# MPU_12x12.net
KiCad netlist of a schematic drawn in Altium Designer
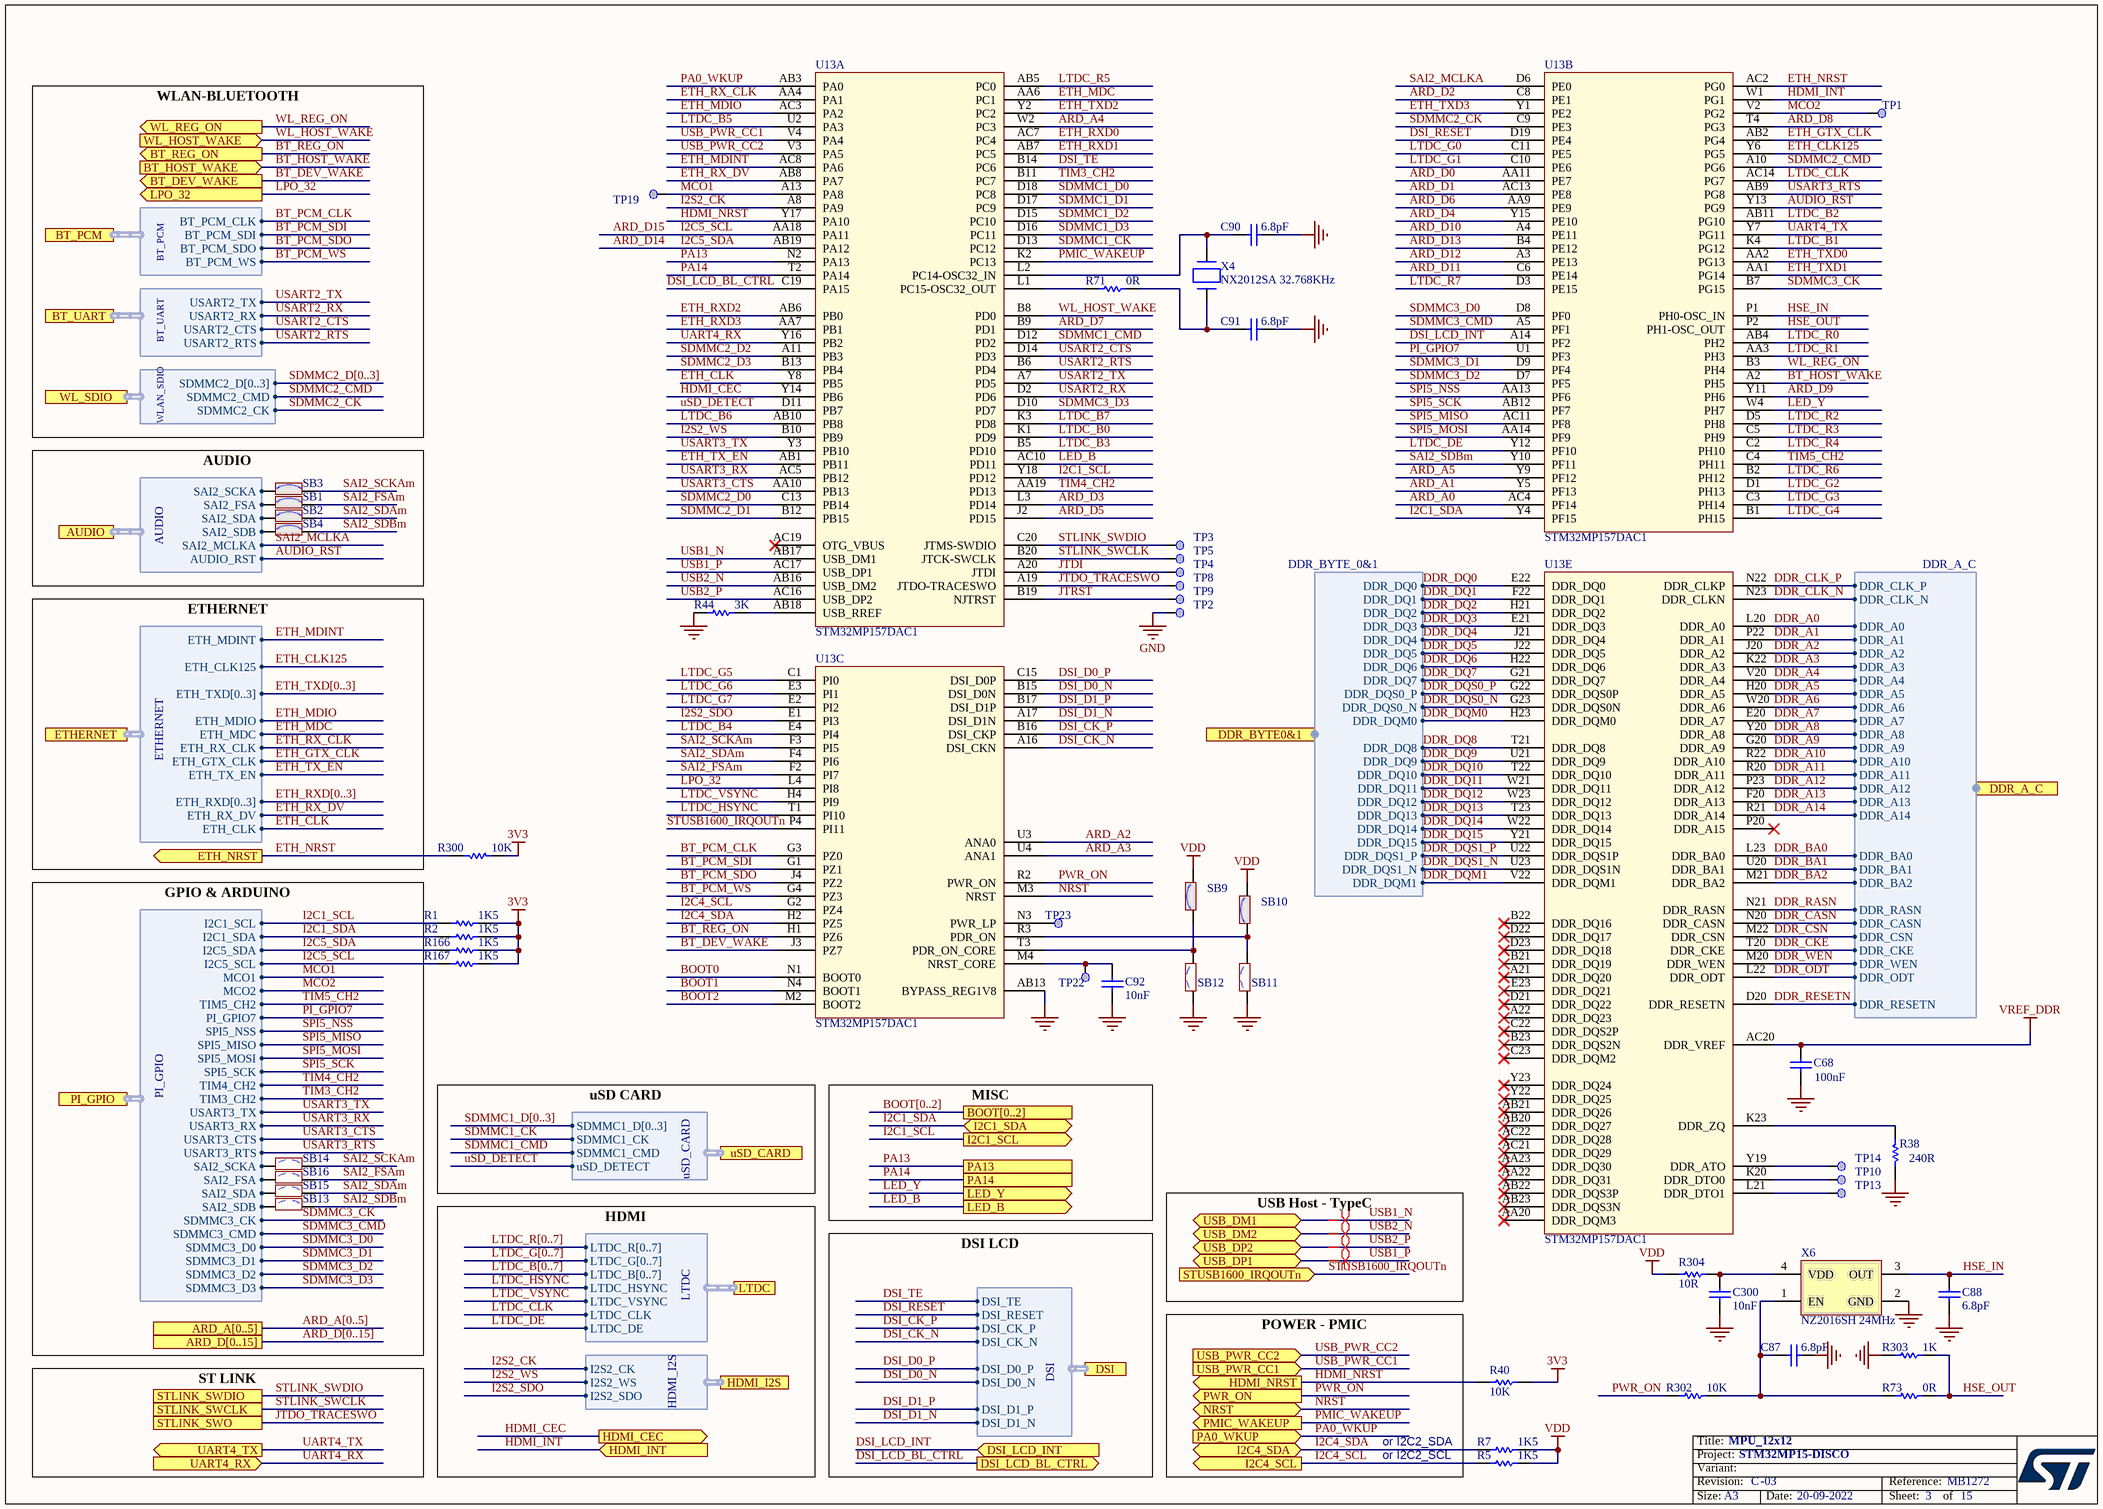
[diagram p0: MPU_12x12.SchDoc]

(export (version "E")
  (design (tool "Eeschema 10.0.6"))
  (components
    (comp (ref "C68")
      (value "100nF")
      (footprint "C0402")
      (description "Capacitor,100nF,16V,X7R,10%,0402")
      (fields
        (field (name "INTERNAL_PART_NUMBER") "MCD-00006")
        (field (name "MANUFACTURER_PART_NUMBER") "CC0402KRX7R7BB104")
        (field (name "PROVIDED_BY") "SUBCO")
      )
      (libsource (lib "MCD_PARTS_database") (part "Capacitor"))
    )
    (comp (ref "C87")
      (value "6.8pF")
      (footprint "C0402")
      (description "Capacitor, MLCC, 6.8pF, 50V, NPO, +-0.25pF, 0402, T=0.5mm")
      (fields
        (field (name "INTERNAL_PART_NUMBER") "MCD-00674")
        (field (name "MANUFACTURER_PART_NUMBER") "CC0402CRNPO9BN6R8")
        (field (name "PROVIDED_BY") "SUBCO")
      )
      (libsource (lib "MCD_PARTS_database") (part "Capacitor"))
    )
    (comp (ref "C88")
      (value "6.8pF")
      (footprint "C0402")
      (description "Capacitor, MLCC, 6.8pF, 50V, NPO, +-0.25pF, 0402, T=0.5mm")
      (fields
        (field (name "INTERNAL_PART_NUMBER") "MCD-00674")
        (field (name "MANUFACTURER_PART_NUMBER") "CC0402CRNPO9BN6R8")
        (field (name "PROVIDED_BY") "SUBCO")
      )
      (libsource (lib "MCD_PARTS_database") (part "Capacitor"))
    )
    (comp (ref "C90")
      (value "6.8pF")
      (footprint "C0402")
      (description "Capacitor, MLCC, 6.8pF, 50V, NPO, +-0.25pF, 0402, T=0.5mm")
      (fields
        (field (name "INTERNAL_PART_NUMBER") "MCD-00674")
        (field (name "MANUFACTURER_PART_NUMBER") "CC0402CRNPO9BN6R8")
        (field (name "PROVIDED_BY") "SUBCO")
      )
      (libsource (lib "MCD_PARTS_database") (part "Capacitor"))
    )
    (comp (ref "C91")
      (value "6.8pF")
      (footprint "C0402")
      (description "Capacitor, MLCC, 6.8pF, 50V, NPO, +-0.25pF, 0402, T=0.5mm")
      (fields
        (field (name "INTERNAL_PART_NUMBER") "MCD-00674")
        (field (name "MANUFACTURER_PART_NUMBER") "CC0402CRNPO9BN6R8")
        (field (name "PROVIDED_BY") "SUBCO")
      )
      (libsource (lib "MCD_PARTS_database") (part "Capacitor"))
    )
    (comp (ref "C92")
      (value "10nF")
      (footprint "C0402")
      (description "Capacitor, MLCC, 10nF, 16V, X7R, 10%, 0402, T=0.5mm")
      (fields
        (field (name "INTERNAL_PART_NUMBER") "MCD-00011")
        (field (name "MANUFACTURER_PART_NUMBER") "CC0402KRX7R7BB103")
        (field (name "PROVIDED_BY") "SUBCO")
      )
      (libsource (lib "MCD_PARTS_database") (part "Capacitor"))
    )
    (comp (ref "C300")
      (value "10nF")
      (footprint "C0402")
      (description "Capacitor, MLCC, 10nF, 16V, X7R, 10%, 0402, T=0.5mm")
      (fields
        (field (name "INTERNAL_PART_NUMBER") "MCD-00011")
        (field (name "MANUFACTURER_PART_NUMBER") "CC0402KRX7R7BB103")
        (field (name "PROVIDED_BY") "SUBCO")
      )
      (libsource (lib "MCD_PARTS_database") (part "Capacitor"))
    )
    (comp (ref "R1")
      (value "1K5")
      (footprint "R0402")
      (description "Resistor,1K5,0402,1%,1/16W")
      (fields
        (field (name "INTERNAL_PART_NUMBER") "MCD-00068")
        (field (name "MANUFACTURER_PART_NUMBER") "RC0402FR-071K5L")
        (field (name "PROVIDED_BY") "SUBCO")
      )
      (libsource (lib "MCD_PARTS_database") (part "Resistor"))
    )
    (comp (ref "R2")
      (value "1K5")
      (footprint "R0402")
      (description "Resistor,1K5,0402,1%,1/16W")
      (fields
        (field (name "INTERNAL_PART_NUMBER") "MCD-00068")
        (field (name "MANUFACTURER_PART_NUMBER") "RC0402FR-071K5L")
        (field (name "PROVIDED_BY") "SUBCO")
      )
      (libsource (lib "MCD_PARTS_database") (part "Resistor"))
    )
    (comp (ref "R5")
      (value "1K5")
      (footprint "R0402")
      (description "Resistor,1K5,0402,1%,1/16W")
      (fields
        (field (name "INTERNAL_PART_NUMBER") "MCD-00068")
        (field (name "MANUFACTURER_PART_NUMBER") "RC0402FR-071K5L")
        (field (name "PROVIDED_BY") "SUBCO")
      )
      (libsource (lib "MCD_PARTS_database") (part "Resistor"))
    )
    (comp (ref "R7")
      (value "1K5")
      (footprint "R0402")
      (description "Resistor,1K5,0402,1%,1/16W")
      (fields
        (field (name "INTERNAL_PART_NUMBER") "MCD-00068")
        (field (name "MANUFACTURER_PART_NUMBER") "RC0402FR-071K5L")
        (field (name "PROVIDED_BY") "SUBCO")
      )
      (libsource (lib "MCD_PARTS_database") (part "Resistor"))
    )
    (comp (ref "R38")
      (value "240R")
      (footprint "R0402")
      (description "Resistor,240R,0402,1%,1/16W")
      (fields
        (field (name "INTERNAL_PART_NUMBER") "MCD-00120")
        (field (name "MANUFACTURER_PART_NUMBER") "RC0402FR-07240RL")
        (field (name "PROVIDED_BY") "SUBCO")
      )
      (libsource (lib "MCD_PARTS_database") (part "Resistor"))
    )
    (comp (ref "R40")
      (value "10K")
      (footprint "R0402")
      (description "Resistor,10K,0402,1%,1/16W")
      (fields
        (field (name "INTERNAL_PART_NUMBER") "MCD-00053")
        (field (name "MANUFACTURER_PART_NUMBER") "RC0402FR-0710KL")
        (field (name "PROVIDED_BY") "SUBCO")
      )
      (libsource (lib "MCD_PARTS_database") (part "Resistor"))
    )
    (comp (ref "R44")
      (value "3K")
      (footprint "R0402")
      (description "Resistor,3K,0402,1%,1/16W")
      (fields
        (field (name "INTERNAL_PART_NUMBER") "MCD-00185")
        (field (name "MANUFACTURER_PART_NUMBER") "RC0402FR-073KL")
        (field (name "PROVIDED_BY") "SUBCO")
      )
      (libsource (lib "MCD_PARTS_database") (part "Resistor"))
    )
    (comp (ref "R71")
      (value "0R")
      (footprint "R0402")
      (description "Resistor,0R,0402,5%,1/16W")
      (fields
        (field (name "INTERNAL_PART_NUMBER") "MCD-00052")
        (field (name "MANUFACTURER_PART_NUMBER") "RC0402JR-070RL")
        (field (name "PROVIDED_BY") "SUBCO")
      )
      (libsource (lib "MCD_PARTS_database") (part "Resistor"))
    )
    (comp (ref "R73")
      (value "0R")
      (footprint "R0402")
      (description "Resistor,0R,0402,5%,1/16W")
      (fields
        (field (name "INTERNAL_PART_NUMBER") "MCD-00052")
        (field (name "MANUFACTURER_PART_NUMBER") "RC0402JR-070RL")
        (field (name "PROVIDED_BY") "SUBCO")
      )
      (libsource (lib "MCD_PARTS_database") (part "Resistor"))
    )
    (comp (ref "R166")
      (value "1K5")
      (footprint "R0402")
      (description "Resistor,1K5,0402,1%,1/16W")
      (fields
        (field (name "INTERNAL_PART_NUMBER") "MCD-00068")
        (field (name "MANUFACTURER_PART_NUMBER") "RC0402FR-071K5L")
        (field (name "PROVIDED_BY") "SUBCO")
      )
      (libsource (lib "MCD_PARTS_database") (part "Resistor"))
    )
    (comp (ref "R167")
      (value "1K5")
      (footprint "R0402")
      (description "Resistor,1K5,0402,1%,1/16W")
      (fields
        (field (name "INTERNAL_PART_NUMBER") "MCD-00068")
        (field (name "MANUFACTURER_PART_NUMBER") "RC0402FR-071K5L")
        (field (name "PROVIDED_BY") "SUBCO")
      )
      (libsource (lib "MCD_PARTS_database") (part "Resistor"))
    )
    (comp (ref "R300")
      (value "10K")
      (footprint "R0402")
      (description "Resistor,10K,0402,1%,1/16W")
      (fields
        (field (name "INTERNAL_PART_NUMBER") "MCD-00053")
        (field (name "MANUFACTURER_PART_NUMBER") "RC0402FR-0710KL")
        (field (name "PROVIDED_BY") "SUBCO")
      )
      (libsource (lib "MCD_PARTS_database") (part "Resistor"))
    )
    (comp (ref "R302")
      (value "10K")
      (footprint "R0402")
      (description "Resistor,10K,0402,1%,1/16W")
      (fields
        (field (name "INTERNAL_PART_NUMBER") "MCD-00053")
        (field (name "MANUFACTURER_PART_NUMBER") "RC0402FR-0710KL")
        (field (name "PROVIDED_BY") "SUBCO")
      )
      (libsource (lib "MCD_PARTS_database") (part "Resistor"))
    )
    (comp (ref "R303")
      (value "1K")
      (footprint "R0402")
      (description "Resistor,1K,0402,1%,1/16W")
      (fields
        (field (name "INTERNAL_PART_NUMBER") "MCD-00061")
        (field (name "MANUFACTURER_PART_NUMBER") "RC0402FR-071KL")
        (field (name "PROVIDED_BY") "SUBCO")
      )
      (libsource (lib "MCD_PARTS_database") (part "Resistor"))
    )
    (comp (ref "R304")
      (value "10R")
      (footprint "R0402")
      (description "Resistor,10R,0402,1%,1/16W")
      (fields
        (field (name "INTERNAL_PART_NUMBER") "MCD-00358")
        (field (name "MANUFACTURER_PART_NUMBER") "RC0402FR-0710RL")
        (field (name "PROVIDED_BY") "SUBCO")
      )
      (libsource (lib "MCD_PARTS_database") (part "Resistor"))
    )
    (comp (ref "SB1")
      (value "~")
      (footprint "SOLDER-BRIDGE_R0603-0R")
      (description "Solder Bridge ON")
      (fields
        (field (name "INTERNAL_PART_NUMBER") "MCD-00071")
        (field (name "MANUFACTURER") "YAGEO")
        (field (name "PROVIDED_BY") "SUBCO")
      )
      (libsource (lib "MCD_PARTS_database") (part "SB_ON"))
    )
    (comp (ref "SB2")
      (value "~")
      (footprint "SOLDER-BRIDGE_R0603-0R")
      (description "Solder Bridge ON")
      (fields
        (field (name "INTERNAL_PART_NUMBER") "MCD-00071")
        (field (name "MANUFACTURER") "YAGEO")
        (field (name "PROVIDED_BY") "SUBCO")
      )
      (libsource (lib "MCD_PARTS_database") (part "SB_ON"))
    )
    (comp (ref "SB3")
      (value "~")
      (footprint "SOLDER-BRIDGE_R0603-0R")
      (description "Solder Bridge ON")
      (fields
        (field (name "INTERNAL_PART_NUMBER") "MCD-00071")
        (field (name "MANUFACTURER") "YAGEO")
        (field (name "PROVIDED_BY") "SUBCO")
      )
      (libsource (lib "MCD_PARTS_database") (part "SB_ON"))
    )
    (comp (ref "SB4")
      (value "~")
      (footprint "SOLDER-BRIDGE_R0603-0R")
      (description "Solder Bridge ON")
      (fields
        (field (name "INTERNAL_PART_NUMBER") "MCD-00071")
        (field (name "MANUFACTURER") "YAGEO")
        (field (name "PROVIDED_BY") "SUBCO")
      )
      (libsource (lib "MCD_PARTS_database") (part "SB_ON"))
    )
    (comp (ref "SB9")
      (value "~")
      (footprint "SOLDER-BRIDGE_R0603-0R")
      (description "Solder Bridge ON")
      (fields
        (field (name "INTERNAL_PART_NUMBER") "MCD-00071")
        (field (name "MANUFACTURER") "YAGEO")
        (field (name "PROVIDED_BY") "SUBCO")
      )
      (libsource (lib "") (part "SB_ON_1"))
    )
    (comp (ref "SB10")
      (value "~")
      (footprint "SOLDER-BRIDGE_R0603-0R")
      (description "Solder Bridge ON")
      (fields
        (field (name "INTERNAL_PART_NUMBER") "MCD-00071")
        (field (name "MANUFACTURER") "YAGEO")
        (field (name "PROVIDED_BY") "SUBCO")
      )
      (libsource (lib "") (part "SB_ON_1"))
    )
    (comp (ref "SB11")
      (value "~")
      (footprint "SOLDER-BRIDGE_R0603-0R")
      (description "Solder Bridge OFF")
      (fields
        (field (name "INTERNAL_PART_NUMBER") "MCD-00072")
        (field (name "MANUFACTURER") "YAGEO")
        (field (name "PROVIDED_BY") "SUBCO")
      )
      (libsource (lib "") (part "SB_OFF_1"))
    )
    (comp (ref "SB12")
      (value "~")
      (footprint "SOLDER-BRIDGE_R0603-0R")
      (description "Solder Bridge OFF")
      (fields
        (field (name "INTERNAL_PART_NUMBER") "MCD-00072")
        (field (name "MANUFACTURER") "YAGEO")
        (field (name "PROVIDED_BY") "SUBCO")
      )
      (libsource (lib "") (part "SB_OFF_1"))
    )
    (comp (ref "SB13")
      (value "~")
      (footprint "SOLDER-BRIDGE_R0603-0R")
      (description "Solder Bridge OFF")
      (fields
        (field (name "INTERNAL_PART_NUMBER") "MCD-00072")
        (field (name "MANUFACTURER") "YAGEO")
        (field (name "PROVIDED_BY") "SUBCO")
      )
      (libsource (lib "MCD_PARTS_database") (part "SB_OFF"))
    )
    (comp (ref "SB14")
      (value "~")
      (footprint "SOLDER-BRIDGE_R0603-0R")
      (description "Solder Bridge OFF")
      (fields
        (field (name "INTERNAL_PART_NUMBER") "MCD-00072")
        (field (name "MANUFACTURER") "YAGEO")
        (field (name "PROVIDED_BY") "SUBCO")
      )
      (libsource (lib "MCD_PARTS_database") (part "SB_OFF"))
    )
    (comp (ref "SB15")
      (value "~")
      (footprint "SOLDER-BRIDGE_R0603-0R")
      (description "Solder Bridge OFF")
      (fields
        (field (name "INTERNAL_PART_NUMBER") "MCD-00072")
        (field (name "MANUFACTURER") "YAGEO")
        (field (name "PROVIDED_BY") "SUBCO")
      )
      (libsource (lib "MCD_PARTS_database") (part "SB_OFF"))
    )
    (comp (ref "SB16")
      (value "~")
      (footprint "SOLDER-BRIDGE_R0603-0R")
      (description "Solder Bridge OFF")
      (fields
        (field (name "INTERNAL_PART_NUMBER") "MCD-00072")
        (field (name "MANUFACTURER") "YAGEO")
        (field (name "PROVIDED_BY") "SUBCO")
      )
      (libsource (lib "MCD_PARTS_database") (part "SB_OFF"))
    )
    (comp (ref "TP1")
      (value "Test Point")
      (footprint "TP_SMD_1MM")
      (description "Test Point 1mm")
      (fields
        (field (name "INTERNAL_PART_NUMBER") "MCD-00074")
        (field (name "MANUFACTURER_PART_NUMBER") "n/a")
      )
      (libsource (lib "MCD_PARTS_database") (part "Test Point"))
    )
    (comp (ref "TP2")
      (value "Test Point")
      (footprint "TP_SMD_1MM")
      (description "Test Point 1mm")
      (fields
        (field (name "INTERNAL_PART_NUMBER") "MCD-00074")
        (field (name "MANUFACTURER_PART_NUMBER") "n/a")
      )
      (libsource (lib "MCD_PARTS_database") (part "Test Point"))
    )
    (comp (ref "TP3")
      (value "Test Point")
      (footprint "TP_SMD_1MM")
      (description "Test Point 1mm")
      (fields
        (field (name "INTERNAL_PART_NUMBER") "MCD-00074")
        (field (name "MANUFACTURER_PART_NUMBER") "n/a")
      )
      (libsource (lib "MCD_PARTS_database") (part "Test Point"))
    )
    (comp (ref "TP4")
      (value "Test Point")
      (footprint "TP_SMD_1MM")
      (description "Test Point 1mm")
      (fields
        (field (name "INTERNAL_PART_NUMBER") "MCD-00074")
        (field (name "MANUFACTURER_PART_NUMBER") "n/a")
      )
      (libsource (lib "MCD_PARTS_database") (part "Test Point"))
    )
    (comp (ref "TP5")
      (value "Test Point")
      (footprint "TP_SMD_1MM")
      (description "Test Point 1mm")
      (fields
        (field (name "INTERNAL_PART_NUMBER") "MCD-00074")
        (field (name "MANUFACTURER_PART_NUMBER") "n/a")
      )
      (libsource (lib "MCD_PARTS_database") (part "Test Point"))
    )
    (comp (ref "TP8")
      (value "Test Point")
      (footprint "TP_SMD_1MM")
      (description "Test Point 1mm")
      (fields
        (field (name "INTERNAL_PART_NUMBER") "MCD-00074")
        (field (name "MANUFACTURER_PART_NUMBER") "n/a")
      )
      (libsource (lib "MCD_PARTS_database") (part "Test Point"))
    )
    (comp (ref "TP9")
      (value "Test Point")
      (footprint "TP_SMD_1MM")
      (description "Test Point 1mm")
      (fields
        (field (name "INTERNAL_PART_NUMBER") "MCD-00074")
        (field (name "MANUFACTURER_PART_NUMBER") "n/a")
      )
      (libsource (lib "MCD_PARTS_database") (part "Test Point"))
    )
    (comp (ref "TP10")
      (value "~")
      (footprint "TP_SMD_0-6MM")
      (description "Test Point 0.6mm")
      (fields (field (name "INTERNAL_PART_NUMBER") "MCD-00631"))
      (libsource (lib "MCD_PARTS_database") (part "Test Point"))
    )
    (comp (ref "TP13")
      (value "~")
      (footprint "TP_SMD_0-6MM")
      (description "Test Point 0.6mm")
      (fields (field (name "INTERNAL_PART_NUMBER") "MCD-00631"))
      (libsource (lib "MCD_PARTS_database") (part "Test Point"))
    )
    (comp (ref "TP14")
      (value "~")
      (footprint "TP_SMD_0-6MM")
      (description "Test Point 0.6mm")
      (fields (field (name "INTERNAL_PART_NUMBER") "MCD-00631"))
      (libsource (lib "MCD_PARTS_database") (part "Test Point"))
    )
    (comp (ref "TP19")
      (value "Test Point")
      (footprint "TP_SMD_1MM")
      (description "Test Point 1mm")
      (fields
        (field (name "INTERNAL_PART_NUMBER") "MCD-00074")
        (field (name "MANUFACTURER_PART_NUMBER") "n/a")
      )
      (libsource (lib "") (part "Test Point_2"))
    )
    (comp (ref "TP22")
      (value "Test Point")
      (footprint "TP_SMD_1MM")
      (description "Test Point 1mm")
      (fields
        (field (name "INTERNAL_PART_NUMBER") "MCD-00074")
        (field (name "MANUFACTURER_PART_NUMBER") "n/a")
      )
      (libsource (lib "") (part "Test Point_1"))
    )
    (comp (ref "TP23")
      (value "Test Point")
      (footprint "TP_SMD_1MM")
      (description "Test Point 1mm")
      (fields
        (field (name "INTERNAL_PART_NUMBER") "MCD-00074")
        (field (name "MANUFACTURER_PART_NUMBER") "n/a")
      )
      (libsource (lib "MCD_PARTS_database") (part "Test Point"))
    )
    (comp (ref "U13")
      (value "STM32MP157DAC1")
      (footprint "ICC_TFBGA361_12X12_STM32MP157CAC3_P050-065")
      (description "MPU TFBGA12x12 without crypto increased frequency")
      (fields
        (field (name "INTERNAL_PART_NUMBER") "MCD-02020")
        (field (name "MANUFACTURER") "STMICROELECTRONICS")
        (field (name "PROVIDED_BY") "SUBCO with ST control")
      )
      (libsource (lib "MCD_PARTS_database") (part "STM32MP157DAC1"))
    )
    (comp (ref "X4")
      (value "NX2012SA 32.768KHz")
      (footprint "CRY_NX2012SA_2P")
      (description "Crystal 32.768kHz, 6pF, -+20PPM, R=80K, SMD")
      (fields
        (field (name "INTERNAL_PART_NUMBER") "MCD-01479")
        (field (name "MANUFACTURER_PART_NUMBER") "NX2012SA 32.768KHz EXS00A-MU00527")
        (field (name "PROVIDED_BY") "SUBCO")
      )
      (libsource (lib "MCD_PARTS_database") (part "XTAL_2_PINS"))
    )
    (comp (ref "X6")
      (value "NZ2016SH 24MHz")
      (footprint "CRY_NZ2016SH_4P")
      (description "Oscillator 24Mhz, +-50ppm, Vcc:3.3V typ (1.62V min), square wave: [0.1Vcc;0.9Vcc], Enable pin")
      (fields
        (field (name "INTERNAL_PART_NUMBER") "MCD-01627")
        (field (name "MANUFACTURER_PART_NUMBER") "NZ2016SH 24MHz END4869F")
        (field (name "PROVIDED_BY") "SUBCO")
      )
      (libsource (lib "MCD_PARTS_database") (part "OSCILLATOR_4_PINS"))
    )
  )
  (nets
    (net (code "13") (name "/ARD_A0") (class "Default")
      (node (ref "U13") (pin "AC4") (pinfunction "PF14_AC4") (pintype "passive"))
    )
    (net (code "14") (name "/ARD_A1") (class "Default")
      (node (ref "U13") (pin "Y5") (pinfunction "PF13_Y5") (pintype "passive"))
    )
    (net (code "15") (name "/ARD_A2") (class "Default")
      (node (ref "U13") (pin "U3") (pinfunction "ANA0_U3") (pintype "passive"))
    )
    (net (code "16") (name "/ARD_A3") (class "Default")
      (node (ref "U13") (pin "U4") (pinfunction "ANA1_U4") (pintype "passive"))
    )
    (net (code "17") (name "/ARD_A4") (class "Default")
      (node (ref "U13") (pin "W2") (pinfunction "PC3_W2") (pintype "passive"))
    )
    (net (code "18") (name "/ARD_A5") (class "Default")
      (node (ref "U13") (pin "Y9") (pinfunction "PF12_Y9") (pintype "passive"))
    )
    (net (code "20") (name "/ARD_D0") (class "Default")
      (node (ref "U13") (pin "AA11") (pinfunction "PE7_AA11") (pintype "passive"))
    )
    (net (code "21") (name "/ARD_D1") (class "Default")
      (node (ref "U13") (pin "AC13") (pinfunction "PE8_AC13") (pintype "passive"))
    )
    (net (code "22") (name "/ARD_D2") (class "Default")
      (node (ref "U13") (pin "C8") (pinfunction "PE1_C8") (pintype "passive"))
    )
    (net (code "23") (name "/ARD_D3") (class "Default")
      (node (ref "U13") (pin "L3") (pinfunction "PD14_L3") (pintype "passive"))
    )
    (net (code "24") (name "/ARD_D4") (class "Default")
      (node (ref "U13") (pin "Y15") (pinfunction "PE10_Y15") (pintype "passive"))
    )
    (net (code "25") (name "/ARD_D5") (class "Default")
      (node (ref "U13") (pin "J2") (pinfunction "PD15_J2") (pintype "passive"))
    )
    (net (code "26") (name "/ARD_D6") (class "Default")
      (node (ref "U13") (pin "AA9") (pinfunction "PE9_AA9") (pintype "passive"))
    )
    (net (code "27") (name "/ARD_D7") (class "Default")
      (node (ref "U13") (pin "B9") (pinfunction "PD1_B9") (pintype "passive"))
    )
    (net (code "28") (name "/ARD_D8") (class "Default")
      (node (ref "U13") (pin "T4") (pinfunction "PG3_T4") (pintype "passive"))
    )
    (net (code "29") (name "/ARD_D9") (class "Default")
      (node (ref "U13") (pin "Y11") (pinfunction "PH6_Y11") (pintype "passive"))
    )
    (net (code "30") (name "/ARD_D10") (class "Default")
      (node (ref "U13") (pin "A4") (pinfunction "PE11_A4") (pintype "passive"))
    )
    (net (code "31") (name "/ARD_D11") (class "Default")
      (node (ref "U13") (pin "C6") (pinfunction "PE14_C6") (pintype "passive"))
    )
    (net (code "32") (name "/ARD_D12") (class "Default")
      (node (ref "U13") (pin "A3") (pinfunction "PE13_A3") (pintype "passive"))
    )
    (net (code "33") (name "/ARD_D13") (class "Default")
      (node (ref "U13") (pin "B4") (pinfunction "PE12_B4") (pintype "passive"))
    )
    (net (code "34") (name "/ARD_D14") (class "Default")
      (node (ref "R166") (pin "2") (pinfunction "2_2") (pintype "passive"))
      (node (ref "U13") (pin "AB19") (pinfunction "PA12_AB19") (pintype "passive"))
    )
    (net (code "35") (name "/ARD_D15") (class "Default")
      (node (ref "R167") (pin "2") (pinfunction "2_2") (pintype "passive"))
      (node (ref "U13") (pin "AA18") (pinfunction "PA11_AA18") (pintype "passive"))
    )
    (net (code "37") (name "/AUDIO_RST") (class "Default")
      (node (ref "U13") (pin "Y13") (pinfunction "PG9_Y13") (pintype "passive"))
    )
    (net (code "38") (name "/BOOT0") (class "Default")
      (node (ref "U13") (pin "N1") (pinfunction "BOOT0_N1") (pintype "passive"))
    )
    (net (code "39") (name "/BOOT1") (class "Default")
      (node (ref "U13") (pin "N4") (pinfunction "BOOT1_N4") (pintype "passive"))
    )
    (net (code "40") (name "/BOOT2") (class "Default")
      (node (ref "U13") (pin "M2") (pinfunction "BOOT2_M2") (pintype "passive"))
    )
    (net (code "42") (name "/BT_DEV_WAKE") (class "Default")
      (node (ref "U13") (pin "J3") (pinfunction "PZ7_J3") (pintype "passive"))
    )
    (net (code "43") (name "/BT_HOST_WAKE") (class "Default")
      (node (ref "U13") (pin "A2") (pinfunction "PH5_A2") (pintype "passive"))
    )
    (net (code "44") (name "/BT_PCM_CLK") (class "Default")
      (node (ref "U13") (pin "G3") (pinfunction "PZ0_G3") (pintype "passive"))
    )
    (net (code "45") (name "/BT_PCM_SDI") (class "Default")
      (node (ref "U13") (pin "G1") (pinfunction "PZ1_G1") (pintype "passive"))
    )
    (net (code "46") (name "/BT_PCM_SDO") (class "Default")
      (node (ref "U13") (pin "J4") (pinfunction "PZ2_J4") (pintype "passive"))
    )
    (net (code "47") (name "/BT_PCM_WS") (class "Default")
      (node (ref "U13") (pin "G4") (pinfunction "PZ3_G4") (pintype "passive"))
    )
    (net (code "48") (name "/BT_REG_ON") (class "Default")
      (node (ref "U13") (pin "H1") (pinfunction "PZ6_H1") (pintype "passive"))
    )
    (net (code "49") (name "/DDR_A0") (class "Default")
      (node (ref "U13") (pin "L20") (pinfunction "DDR_A0_L20") (pintype "passive"))
    )
    (net (code "50") (name "/DDR_A1") (class "Default")
      (node (ref "U13") (pin "P22") (pinfunction "DDR_A1_P22") (pintype "passive"))
    )
    (net (code "51") (name "/DDR_A2") (class "Default")
      (node (ref "U13") (pin "J20") (pinfunction "DDR_A2_J20") (pintype "passive"))
    )
    (net (code "52") (name "/DDR_A3") (class "Default")
      (node (ref "U13") (pin "K22") (pinfunction "DDR_A3_K22") (pintype "passive"))
    )
    (net (code "53") (name "/DDR_A4") (class "Default")
      (node (ref "U13") (pin "V20") (pinfunction "DDR_A4_V20") (pintype "passive"))
    )
    (net (code "54") (name "/DDR_A5") (class "Default")
      (node (ref "U13") (pin "H20") (pinfunction "DDR_A5_H20") (pintype "passive"))
    )
    (net (code "55") (name "/DDR_A6") (class "Default")
      (node (ref "U13") (pin "W20") (pinfunction "DDR_A6_W20") (pintype "passive"))
    )
    (net (code "56") (name "/DDR_A7") (class "Default")
      (node (ref "U13") (pin "E20") (pinfunction "DDR_A7_E20") (pintype "passive"))
    )
    (net (code "57") (name "/DDR_A8") (class "Default")
      (node (ref "U13") (pin "Y20") (pinfunction "DDR_A8_Y20") (pintype "passive"))
    )
    (net (code "58") (name "/DDR_A9") (class "Default")
      (node (ref "U13") (pin "G20") (pinfunction "DDR_A9_G20") (pintype "passive"))
    )
    (net (code "59") (name "/DDR_A10") (class "Default")
      (node (ref "U13") (pin "R22") (pinfunction "DDR_A10_R22") (pintype "passive"))
    )
    (net (code "60") (name "/DDR_A11") (class "Default")
      (node (ref "U13") (pin "R20") (pinfunction "DDR_A11_R20") (pintype "passive"))
    )
    (net (code "61") (name "/DDR_A12") (class "Default")
      (node (ref "U13") (pin "P23") (pinfunction "DDR_A12_P23") (pintype "passive"))
    )
    (net (code "62") (name "/DDR_A13") (class "Default")
      (node (ref "U13") (pin "F20") (pinfunction "DDR_A13_F20") (pintype "passive"))
    )
    (net (code "63") (name "/DDR_A14") (class "Default")
      (node (ref "U13") (pin "R21") (pinfunction "DDR_A14_R21") (pintype "passive"))
    )
    (net (code "64") (name "/DDR_BA0") (class "Default")
      (node (ref "U13") (pin "L23") (pinfunction "DDR_BA0_L23") (pintype "passive"))
    )
    (net (code "65") (name "/DDR_BA1") (class "Default")
      (node (ref "U13") (pin "U20") (pinfunction "DDR_BA1_U20") (pintype "passive"))
    )
    (net (code "66") (name "/DDR_BA2") (class "Default")
      (node (ref "U13") (pin "M21") (pinfunction "DDR_BA2_M21") (pintype "passive"))
    )
    (net (code "67") (name "/DDR_CASN") (class "Default")
      (node (ref "U13") (pin "N20") (pinfunction "DDR_CASN_N20") (pintype "passive"))
    )
    (net (code "68") (name "/DDR_CKE") (class "Default")
      (node (ref "U13") (pin "T20") (pinfunction "DDR_CKE_T20") (pintype "passive"))
    )
    (net (code "69") (name "/DDR_CLK_N") (class "Default")
      (node (ref "U13") (pin "N23") (pinfunction "DDR_CLKN_N23") (pintype "passive"))
    )
    (net (code "70") (name "/DDR_CLK_P") (class "Default")
      (node (ref "U13") (pin "N22") (pinfunction "DDR_CLKP_N22") (pintype "passive"))
    )
    (net (code "71") (name "/DDR_CSN") (class "Default")
      (node (ref "U13") (pin "M22") (pinfunction "DDR_CSN_M22") (pintype "passive"))
    )
    (net (code "72") (name "/DDR_DQ0") (class "Default")
      (node (ref "U13") (pin "E22") (pinfunction "DDR_DQ0_E22") (pintype "passive"))
    )
    (net (code "73") (name "/DDR_DQ1") (class "Default")
      (node (ref "U13") (pin "F22") (pinfunction "DDR_DQ1_F22") (pintype "passive"))
    )
    (net (code "74") (name "/DDR_DQ2") (class "Default")
      (node (ref "U13") (pin "H21") (pinfunction "DDR_DQ2_H21") (pintype "passive"))
    )
    (net (code "75") (name "/DDR_DQ3") (class "Default")
      (node (ref "U13") (pin "E21") (pinfunction "DDR_DQ3_E21") (pintype "passive"))
    )
    (net (code "76") (name "/DDR_DQ4") (class "Default")
      (node (ref "U13") (pin "J21") (pinfunction "DDR_DQ4_J21") (pintype "passive"))
    )
    (net (code "77") (name "/DDR_DQ5") (class "Default")
      (node (ref "U13") (pin "J22") (pinfunction "DDR_DQ5_J22") (pintype "passive"))
    )
    (net (code "78") (name "/DDR_DQ6") (class "Default")
      (node (ref "U13") (pin "H22") (pinfunction "DDR_DQ6_H22") (pintype "passive"))
    )
    (net (code "79") (name "/DDR_DQ7") (class "Default")
      (node (ref "U13") (pin "G21") (pinfunction "DDR_DQ7_G21") (pintype "passive"))
    )
    (net (code "80") (name "/DDR_DQ8") (class "Default")
      (node (ref "U13") (pin "T21") (pinfunction "DDR_DQ8_T21") (pintype "passive"))
    )
    (net (code "81") (name "/DDR_DQ9") (class "Default")
      (node (ref "U13") (pin "U21") (pinfunction "DDR_DQ9_U21") (pintype "passive"))
    )
    (net (code "82") (name "/DDR_DQ10") (class "Default")
      (node (ref "U13") (pin "T22") (pinfunction "DDR_DQ10_T22") (pintype "passive"))
    )
    (net (code "83") (name "/DDR_DQ11") (class "Default")
      (node (ref "U13") (pin "W21") (pinfunction "DDR_DQ11_W21") (pintype "passive"))
    )
    (net (code "84") (name "/DDR_DQ12") (class "Default")
      (node (ref "U13") (pin "W23") (pinfunction "DDR_DQ12_W23") (pintype "passive"))
    )
    (net (code "85") (name "/DDR_DQ13") (class "Default")
      (node (ref "U13") (pin "T23") (pinfunction "DDR_DQ13_T23") (pintype "passive"))
    )
    (net (code "86") (name "/DDR_DQ14") (class "Default")
      (node (ref "U13") (pin "W22") (pinfunction "DDR_DQ14_W22") (pintype "passive"))
    )
    (net (code "87") (name "/DDR_DQ15") (class "Default")
      (node (ref "U13") (pin "Y21") (pinfunction "DDR_DQ15_Y21") (pintype "passive"))
    )
    (net (code "88") (name "/DDR_DQM0") (class "Default")
      (node (ref "U13") (pin "H23") (pinfunction "DDR_DQM0_H23") (pintype "passive"))
    )
    (net (code "89") (name "/DDR_DQM1") (class "Default")
      (node (ref "U13") (pin "V22") (pinfunction "DDR_DQM1_V22") (pintype "passive"))
    )
    (net (code "90") (name "/DDR_DQS0_N") (class "Default")
      (node (ref "U13") (pin "G23") (pinfunction "DDR_DQS0N_G23") (pintype "passive"))
    )
    (net (code "91") (name "/DDR_DQS0_P") (class "Default")
      (node (ref "U13") (pin "G22") (pinfunction "DDR_DQS0P_G22") (pintype "passive"))
    )
    (net (code "92") (name "/DDR_DQS1_N") (class "Default")
      (node (ref "U13") (pin "U23") (pinfunction "DDR_DQS1N_U23") (pintype "passive"))
    )
    (net (code "93") (name "/DDR_DQS1_P") (class "Default")
      (node (ref "U13") (pin "U22") (pinfunction "DDR_DQS1P_U22") (pintype "passive"))
    )
    (net (code "94") (name "/DDR_ODT") (class "Default")
      (node (ref "U13") (pin "L22") (pinfunction "DDR_ODT_L22") (pintype "passive"))
    )
    (net (code "95") (name "/DDR_RASN") (class "Default")
      (node (ref "U13") (pin "N21") (pinfunction "DDR_RASN_N21") (pintype "passive"))
    )
    (net (code "96") (name "/DDR_RESETN") (class "Default")
      (node (ref "U13") (pin "D20") (pinfunction "DDR_RESETN_D20") (pintype "passive"))
    )
    (net (code "97") (name "/DDR_WEN") (class "Default")
      (node (ref "U13") (pin "M20") (pinfunction "DDR_WEN_M20") (pintype "passive"))
    )
    (net (code "98") (name "/DSI_CK_N") (class "Default")
      (node (ref "U13") (pin "A16") (pinfunction "DSI_CKN_A16") (pintype "passive"))
    )
    (net (code "99") (name "/DSI_CK_P") (class "Default")
      (node (ref "U13") (pin "B16") (pinfunction "DSI_CKP_B16") (pintype "passive"))
    )
    (net (code "100") (name "/DSI_D0_N") (class "Default")
      (node (ref "U13") (pin "B15") (pinfunction "DSI_D0N_B15") (pintype "passive"))
    )
    (net (code "101") (name "/DSI_D0_P") (class "Default")
      (node (ref "U13") (pin "C15") (pinfunction "DSI_D0P_C15") (pintype "passive"))
    )
    (net (code "102") (name "/DSI_D1_N") (class "Default")
      (node (ref "U13") (pin "A17") (pinfunction "DSI_D1N_A17") (pintype "passive"))
    )
    (net (code "103") (name "/DSI_D1_P") (class "Default")
      (node (ref "U13") (pin "B17") (pinfunction "DSI_D1P_B17") (pintype "passive"))
    )
    (net (code "104") (name "/DSI_LCD_BL_CTRL") (class "Default")
      (node (ref "U13") (pin "C19") (pinfunction "PA15_C19") (pintype "passive"))
    )
    (net (code "105") (name "/DSI_LCD_INT") (class "Default")
      (node (ref "U13") (pin "A14") (pinfunction "PF2_A14") (pintype "passive"))
    )
    (net (code "106") (name "/DSI_RESET") (class "Default")
      (node (ref "U13") (pin "D19") (pinfunction "PE4_D19") (pintype "passive"))
    )
    (net (code "107") (name "/DSI_TE") (class "Default")
      (node (ref "U13") (pin "B14") (pinfunction "PC6_B14") (pintype "passive"))
    )
    (net (code "109") (name "/ETH_CLK") (class "Default")
      (node (ref "U13") (pin "Y8") (pinfunction "PB5_Y8") (pintype "passive"))
    )
    (net (code "110") (name "/ETH_CLK125") (class "Default")
      (node (ref "U13") (pin "Y6") (pinfunction "PG5_Y6") (pintype "passive"))
    )
    (net (code "111") (name "/ETH_GTX_CLK") (class "Default")
      (node (ref "U13") (pin "AB2") (pinfunction "PG4_AB2") (pintype "passive"))
    )
    (net (code "112") (name "/ETH_MDC") (class "Default")
      (node (ref "U13") (pin "AA6") (pinfunction "PC1_AA6") (pintype "passive"))
    )
    (net (code "113") (name "/ETH_MDINT") (class "Default")
      (node (ref "U13") (pin "AC8") (pinfunction "PA6_AC8") (pintype "passive"))
    )
    (net (code "114") (name "/ETH_MDIO") (class "Default")
      (node (ref "U13") (pin "AC3") (pinfunction "PA2_AC3") (pintype "passive"))
    )
    (net (code "115") (name "/ETH_NRST") (class "Default")
      (node (ref "R300") (pin "2") (pinfunction "2_2") (pintype "passive"))
      (node (ref "U13") (pin "AC2") (pinfunction "PG0_AC2") (pintype "passive"))
    )
    (net (code "116") (name "/ETH_RXD0") (class "Default")
      (node (ref "U13") (pin "AC7") (pinfunction "PC4_AC7") (pintype "passive"))
    )
    (net (code "117") (name "/ETH_RXD1") (class "Default")
      (node (ref "U13") (pin "AB7") (pinfunction "PC5_AB7") (pintype "passive"))
    )
    (net (code "118") (name "/ETH_RXD2") (class "Default")
      (node (ref "U13") (pin "AB6") (pinfunction "PB0_AB6") (pintype "passive"))
    )
    (net (code "119") (name "/ETH_RXD3") (class "Default")
      (node (ref "U13") (pin "AA7") (pinfunction "PB1_AA7") (pintype "passive"))
    )
    (net (code "120") (name "/ETH_RX_CLK") (class "Default")
      (node (ref "U13") (pin "AA4") (pinfunction "PA1_AA4") (pintype "passive"))
    )
    (net (code "121") (name "/ETH_RX_DV") (class "Default")
      (node (ref "U13") (pin "AB8") (pinfunction "PA7_AB8") (pintype "passive"))
    )
    (net (code "122") (name "/ETH_TXD0") (class "Default")
      (node (ref "U13") (pin "AA2") (pinfunction "PG13_AA2") (pintype "passive"))
    )
    (net (code "123") (name "/ETH_TXD1") (class "Default")
      (node (ref "U13") (pin "AA1") (pinfunction "PG14_AA1") (pintype "passive"))
    )
    (net (code "124") (name "/ETH_TXD2") (class "Default")
      (node (ref "U13") (pin "Y2") (pinfunction "PC2_Y2") (pintype "passive"))
    )
    (net (code "125") (name "/ETH_TXD3") (class "Default")
      (node (ref "U13") (pin "Y1") (pinfunction "PE2_Y1") (pintype "passive"))
    )
    (net (code "127") (name "/ETH_TX_EN") (class "Default")
      (node (ref "U13") (pin "AB1") (pinfunction "PB11_AB1") (pintype "passive"))
    )
    (net (code "128") (name "/HDMI_CEC") (class "Default")
      (node (ref "U13") (pin "Y14") (pinfunction "PB6_Y14") (pintype "passive"))
    )
    (net (code "129") (name "/HDMI_INT") (class "Default")
      (node (ref "U13") (pin "W1") (pinfunction "PG1_W1") (pintype "passive"))
    )
    (net (code "130") (name "/HDMI_NRST") (class "Default")
      (node (ref "R40") (pin "2") (pinfunction "2_2") (pintype "passive"))
      (node (ref "U13") (pin "Y17") (pinfunction "PA10_Y17") (pintype "passive"))
    )
    (net (code "131") (name "/HSE_IN") (class "Default")
      (node (ref "C88") (pin "2") (pinfunction "2_2") (pintype "passive"))
      (node (ref "U13") (pin "P1") (pinfunction "PH0-OSC_IN_P1") (pintype "passive"))
      (node (ref "X6") (pin "3") (pinfunction "OUT_3") (pintype "passive"))
    )
    (net (code "132") (name "/HSE_OUT") (class "Default")
      (node (ref "R303") (pin "1") (pinfunction "1_1") (pintype "passive"))
      (node (ref "R73") (pin "2") (pinfunction "2_2") (pintype "passive"))
      (node (ref "U13") (pin "P2") (pinfunction "PH1-OSC_OUT_P2") (pintype "passive"))
    )
    (net (code "133") (name "/I2C1_SCL") (class "Default")
      (node (ref "R1") (pin "2") (pinfunction "2_2") (pintype "passive"))
      (node (ref "U13") (pin "Y18") (pinfunction "PD12_Y18") (pintype "passive"))
    )
    (net (code "134") (name "/I2C1_SDA") (class "Default")
      (node (ref "R2") (pin "2") (pinfunction "2_2") (pintype "passive"))
      (node (ref "U13") (pin "Y4") (pinfunction "PF15_Y4") (pintype "passive"))
    )
    (net (code "135") (name "/I2C4_SCL") (class "Default")
      (node (ref "R5") (pin "2") (pinfunction "2_2") (pintype "passive"))
      (node (ref "U13") (pin "G2") (pinfunction "PZ4_G2") (pintype "passive"))
    )
    (net (code "136") (name "/I2C4_SDA") (class "Default")
      (node (ref "R7") (pin "2") (pinfunction "2_2") (pintype "passive"))
      (node (ref "U13") (pin "H2") (pinfunction "PZ5_H2") (pintype "passive"))
    )
    (net (code "137") (name "/I2S2_CK") (class "Default")
      (node (ref "U13") (pin "A8") (pinfunction "PA9_A8") (pintype "passive"))
    )
    (net (code "138") (name "/I2S2_SDO") (class "Default")
      (node (ref "U13") (pin "E1") (pinfunction "PI3_E1") (pintype "passive"))
    )
    (net (code "139") (name "/I2S2_WS") (class "Default")
      (node (ref "U13") (pin "B10") (pinfunction "PB9_B10") (pintype "passive"))
    )
    (net (code "140") (name "/JTDI") (class "Default")
      (node (ref "TP4") (pin "1") (pinfunction "1_1") (pintype "passive"))
      (node (ref "U13") (pin "A20") (pinfunction "JTDI_A20") (pintype "passive"))
    )
    (net (code "141") (name "/JTDO_TRACESWO") (class "Default")
      (node (ref "TP8") (pin "1") (pinfunction "1_1") (pintype "passive"))
      (node (ref "U13") (pin "A19") (pinfunction "JTDO-TRACESWO_A19") (pintype "passive"))
    )
    (net (code "142") (name "/JTRST") (class "Default")
      (node (ref "TP9") (pin "1") (pinfunction "1_1") (pintype "passive"))
      (node (ref "U13") (pin "B19") (pinfunction "NJTRST_B19") (pintype "passive"))
    )
    (net (code "143") (name "/LED_B") (class "Default")
      (node (ref "U13") (pin "AC10") (pinfunction "PD11_AC10") (pintype "passive"))
    )
    (net (code "144") (name "/LED_Y") (class "Default")
      (node (ref "U13") (pin "W4") (pinfunction "PH7_W4") (pintype "passive"))
    )
    (net (code "145") (name "/LPO_32") (class "Default")
      (node (ref "U13") (pin "L4") (pinfunction "PI8_L4") (pintype "passive"))
    )
    (net (code "146") (name "/LTDC_B0") (class "Default")
      (node (ref "U13") (pin "K1") (pinfunction "PD9_K1") (pintype "passive"))
    )
    (net (code "147") (name "/LTDC_B1") (class "Default")
      (node (ref "U13") (pin "K4") (pinfunction "PG12_K4") (pintype "passive"))
    )
    (net (code "148") (name "/LTDC_B2") (class "Default")
      (node (ref "U13") (pin "AB11") (pinfunction "PG10_AB11") (pintype "passive"))
    )
    (net (code "149") (name "/LTDC_B3") (class "Default")
      (node (ref "U13") (pin "B5") (pinfunction "PD10_B5") (pintype "passive"))
    )
    (net (code "150") (name "/LTDC_B4") (class "Default")
      (node (ref "U13") (pin "E4") (pinfunction "PI4_E4") (pintype "passive"))
    )
    (net (code "151") (name "/LTDC_B5") (class "Default")
      (node (ref "U13") (pin "U2") (pinfunction "PA3_U2") (pintype "passive"))
    )
    (net (code "152") (name "/LTDC_B6") (class "Default")
      (node (ref "U13") (pin "AB10") (pinfunction "PB8_AB10") (pintype "passive"))
    )
    (net (code "153") (name "/LTDC_B7") (class "Default")
      (node (ref "U13") (pin "K3") (pinfunction "PD8_K3") (pintype "passive"))
    )
    (net (code "155") (name "/LTDC_CLK") (class "Default")
      (node (ref "U13") (pin "AC14") (pinfunction "PG7_AC14") (pintype "passive"))
    )
    (net (code "156") (name "/LTDC_DE") (class "Default")
      (node (ref "U13") (pin "Y12") (pinfunction "PF10_Y12") (pintype "passive"))
    )
    (net (code "157") (name "/LTDC_G0") (class "Default")
      (node (ref "U13") (pin "C11") (pinfunction "PE5_C11") (pintype "passive"))
    )
    (net (code "158") (name "/LTDC_G1") (class "Default")
      (node (ref "U13") (pin "C10") (pinfunction "PE6_C10") (pintype "passive"))
    )
    (net (code "159") (name "/LTDC_G2") (class "Default")
      (node (ref "U13") (pin "D1") (pinfunction "PH13_D1") (pintype "passive"))
    )
    (net (code "160") (name "/LTDC_G3") (class "Default")
      (node (ref "U13") (pin "C3") (pinfunction "PH14_C3") (pintype "passive"))
    )
    (net (code "161") (name "/LTDC_G4") (class "Default")
      (node (ref "U13") (pin "B1") (pinfunction "PH15_B1") (pintype "passive"))
    )
    (net (code "162") (name "/LTDC_G5") (class "Default")
      (node (ref "U13") (pin "C1") (pinfunction "PI0_C1") (pintype "passive"))
    )
    (net (code "163") (name "/LTDC_G6") (class "Default")
      (node (ref "U13") (pin "E3") (pinfunction "PI1_E3") (pintype "passive"))
    )
    (net (code "164") (name "/LTDC_G7") (class "Default")
      (node (ref "U13") (pin "E2") (pinfunction "PI2_E2") (pintype "passive"))
    )
    (net (code "166") (name "/LTDC_HSYNC") (class "Default")
      (node (ref "U13") (pin "T1") (pinfunction "PI10_T1") (pintype "passive"))
    )
    (net (code "167") (name "/LTDC_R0") (class "Default")
      (node (ref "U13") (pin "AB4") (pinfunction "PH2_AB4") (pintype "passive"))
    )
    (net (code "168") (name "/LTDC_R1") (class "Default")
      (node (ref "U13") (pin "AA3") (pinfunction "PH3_AA3") (pintype "passive"))
    )
    (net (code "169") (name "/LTDC_R2") (class "Default")
      (node (ref "U13") (pin "D5") (pinfunction "PH8_D5") (pintype "passive"))
    )
    (net (code "170") (name "/LTDC_R3") (class "Default")
      (node (ref "U13") (pin "C5") (pinfunction "PH9_C5") (pintype "passive"))
    )
    (net (code "171") (name "/LTDC_R4") (class "Default")
      (node (ref "U13") (pin "C2") (pinfunction "PH10_C2") (pintype "passive"))
    )
    (net (code "172") (name "/LTDC_R5") (class "Default")
      (node (ref "U13") (pin "AB5") (pinfunction "PC0_AB5") (pintype "passive"))
    )
    (net (code "173") (name "/LTDC_R6") (class "Default")
      (node (ref "U13") (pin "B2") (pinfunction "PH12_B2") (pintype "passive"))
    )
    (net (code "174") (name "/LTDC_R7") (class "Default")
      (node (ref "U13") (pin "D3") (pinfunction "PE15_D3") (pintype "passive"))
    )
    (net (code "176") (name "/LTDC_VSYNC") (class "Default")
      (node (ref "U13") (pin "H4") (pinfunction "PI9_H4") (pintype "passive"))
    )
    (net (code "177") (name "/MCO1") (class "Default")
      (node (ref "TP19") (pin "1") (pinfunction "1_1") (pintype "passive"))
      (node (ref "U13") (pin "A13") (pinfunction "PA8_A13") (pintype "passive"))
    )
    (net (code "178") (name "/MCO2") (class "Default")
      (node (ref "TP1") (pin "1") (pinfunction "1_1") (pintype "passive"))
      (node (ref "U13") (pin "V2") (pinfunction "PG2_V2") (pintype "passive"))
    )
    (net (code "179") (name "/NRST") (class "Default")
      (node (ref "U13") (pin "M3") (pinfunction "NRST_M3") (pintype "passive"))
    )
    (net (code "180") (name "/PA0_WKUP") (class "Default")
      (node (ref "U13") (pin "AB3") (pinfunction "PA0_AB3") (pintype "passive"))
    )
    (net (code "181") (name "/PA13") (class "Default")
      (node (ref "U13") (pin "N2") (pinfunction "PA13_N2") (pintype "passive"))
    )
    (net (code "182") (name "/PA14") (class "Default")
      (node (ref "U13") (pin "T2") (pinfunction "PA14_T2") (pintype "passive"))
    )
    (net (code "183") (name "/PI_GPIO7") (class "Default")
      (node (ref "U13") (pin "U1") (pinfunction "PF3_U1") (pintype "passive"))
    )
    (net (code "184") (name "/PMIC_WAKEUP") (class "Default")
      (node (ref "U13") (pin "K2") (pinfunction "PC13_K2") (pintype "passive"))
    )
    (net (code "185") (name "/PWR_ON") (class "Default")
      (node (ref "R302") (pin "2") (pinfunction "2_2") (pintype "passive"))
      (node (ref "U13") (pin "R2") (pinfunction "PWR_ON_R2") (pintype "passive"))
    )
    (net (code "186") (name "/SAI2_FSAm") (class "Default")
      (node (ref "SB1") (pin "2") (pinfunction "2_2") (pintype "passive"))
      (node (ref "SB16") (pin "2") (pinfunction "2_2") (pintype "passive"))
      (node (ref "U13") (pin "F2") (pinfunction "PI7_F2") (pintype "passive"))
    )
    (net (code "187") (name "/SAI2_MCLKA") (class "Default")
      (node (ref "U13") (pin "D6") (pinfunction "PE0_D6") (pintype "passive"))
    )
    (net (code "188") (name "/SAI2_SCKAm") (class "Default")
      (node (ref "SB14") (pin "2") (pinfunction "2_2") (pintype "passive"))
      (node (ref "SB3") (pin "2") (pinfunction "2_2") (pintype "passive"))
      (node (ref "U13") (pin "F3") (pinfunction "PI5_F3") (pintype "passive"))
    )
    (net (code "189") (name "/SAI2_SDAm") (class "Default")
      (node (ref "SB15") (pin "2") (pinfunction "2_2") (pintype "passive"))
      (node (ref "SB2") (pin "2") (pinfunction "2_2") (pintype "passive"))
      (node (ref "U13") (pin "F4") (pinfunction "PI6_F4") (pintype "passive"))
    )
    (net (code "190") (name "/SAI2_SDBm") (class "Default")
      (node (ref "SB13") (pin "2") (pinfunction "2_2") (pintype "passive"))
      (node (ref "SB4") (pin "2") (pinfunction "2_2") (pintype "passive"))
      (node (ref "U13") (pin "Y10") (pinfunction "PF11_Y10") (pintype "passive"))
    )
    (net (code "191") (name "/SDMMC1_CK") (class "Default")
      (node (ref "U13") (pin "D13") (pinfunction "PC12_D13") (pintype "passive"))
    )
    (net (code "192") (name "/SDMMC1_CMD") (class "Default")
      (node (ref "U13") (pin "D12") (pinfunction "PD2_D12") (pintype "passive"))
    )
    (net (code "193") (name "/SDMMC1_D0") (class "Default")
      (node (ref "U13") (pin "D18") (pinfunction "PC8_D18") (pintype "passive"))
    )
    (net (code "194") (name "/SDMMC1_D1") (class "Default")
      (node (ref "U13") (pin "D17") (pinfunction "PC9_D17") (pintype "passive"))
    )
    (net (code "195") (name "/SDMMC1_D2") (class "Default")
      (node (ref "U13") (pin "D15") (pinfunction "PC10_D15") (pintype "passive"))
    )
    (net (code "196") (name "/SDMMC1_D3") (class "Default")
      (node (ref "U13") (pin "D16") (pinfunction "PC11_D16") (pintype "passive"))
    )
    (net (code "198") (name "/SDMMC2_CK") (class "Default")
      (node (ref "U13") (pin "C9") (pinfunction "PE3_C9") (pintype "passive"))
    )
    (net (code "199") (name "/SDMMC2_CMD") (class "Default")
      (node (ref "U13") (pin "A10") (pinfunction "PG6_A10") (pintype "passive"))
    )
    (net (code "200") (name "/SDMMC2_D0") (class "Default")
      (node (ref "U13") (pin "C13") (pinfunction "PB14_C13") (pintype "passive"))
    )
    (net (code "201") (name "/SDMMC2_D1") (class "Default")
      (node (ref "U13") (pin "B12") (pinfunction "PB15_B12") (pintype "passive"))
    )
    (net (code "202") (name "/SDMMC2_D2") (class "Default")
      (node (ref "U13") (pin "A11") (pinfunction "PB3_A11") (pintype "passive"))
    )
    (net (code "203") (name "/SDMMC2_D3") (class "Default")
      (node (ref "U13") (pin "B13") (pinfunction "PB4_B13") (pintype "passive"))
    )
    (net (code "205") (name "/SDMMC3_CK") (class "Default")
      (node (ref "U13") (pin "B7") (pinfunction "PG15_B7") (pintype "passive"))
    )
    (net (code "206") (name "/SDMMC3_CMD") (class "Default")
      (node (ref "U13") (pin "A5") (pinfunction "PF1_A5") (pintype "passive"))
    )
    (net (code "207") (name "/SDMMC3_D0") (class "Default")
      (node (ref "U13") (pin "D8") (pinfunction "PF0_D8") (pintype "passive"))
    )
    (net (code "208") (name "/SDMMC3_D1") (class "Default")
      (node (ref "U13") (pin "D9") (pinfunction "PF4_D9") (pintype "passive"))
    )
    (net (code "209") (name "/SDMMC3_D2") (class "Default")
      (node (ref "U13") (pin "D7") (pinfunction "PF5_D7") (pintype "passive"))
    )
    (net (code "210") (name "/SDMMC3_D3") (class "Default")
      (node (ref "U13") (pin "D10") (pinfunction "PD7_D10") (pintype "passive"))
    )
    (net (code "211") (name "/SPI5_MISO") (class "Default")
      (node (ref "U13") (pin "AC11") (pinfunction "PF8_AC11") (pintype "passive"))
    )
    (net (code "212") (name "/SPI5_MOSI") (class "Default")
      (node (ref "U13") (pin "AA14") (pinfunction "PF9_AA14") (pintype "passive"))
    )
    (net (code "213") (name "/SPI5_NSS") (class "Default")
      (node (ref "U13") (pin "AA13") (pinfunction "PF6_AA13") (pintype "passive"))
    )
    (net (code "214") (name "/SPI5_SCK") (class "Default")
      (node (ref "U13") (pin "AB12") (pinfunction "PF7_AB12") (pintype "passive"))
    )
    (net (code "215") (name "/STLINK_SWCLK") (class "Default")
      (node (ref "TP5") (pin "1") (pinfunction "1_1") (pintype "passive"))
      (node (ref "U13") (pin "B20") (pinfunction "JTCK-SWCLK_B20") (pintype "passive"))
    )
    (net (code "216") (name "/STLINK_SWDIO") (class "Default")
      (node (ref "TP3") (pin "1") (pinfunction "1_1") (pintype "passive"))
      (node (ref "U13") (pin "C20") (pinfunction "JTMS-SWDIO_C20") (pintype "passive"))
    )
    (net (code "217") (name "/STUSB1600_IRQOUTn") (class "Default")
      (node (ref "U13") (pin "P4") (pinfunction "PI11_P4") (pintype "passive"))
    )
    (net (code "218") (name "/TIM3_CH2") (class "Default")
      (node (ref "U13") (pin "B11") (pinfunction "PC7_B11") (pintype "passive"))
    )
    (net (code "219") (name "/TIM4_CH2") (class "Default")
      (node (ref "U13") (pin "AA19") (pinfunction "PD13_AA19") (pintype "passive"))
    )
    (net (code "220") (name "/TIM5_CH2") (class "Default")
      (node (ref "U13") (pin "C4") (pinfunction "PH11_C4") (pintype "passive"))
    )
    (net (code "221") (name "/UART4_RX") (class "Default")
      (node (ref "U13") (pin "Y16") (pinfunction "PB2_Y16") (pintype "passive"))
    )
    (net (code "222") (name "/UART4_TX") (class "Default")
      (node (ref "U13") (pin "Y7") (pinfunction "PG11_Y7") (pintype "passive"))
    )
    (net (code "223") (name "/USART2_CTS") (class "Default")
      (node (ref "U13") (pin "D14") (pinfunction "PD3_D14") (pintype "passive"))
    )
    (net (code "224") (name "/USART2_RTS") (class "Default")
      (node (ref "U13") (pin "B6") (pinfunction "PD4_B6") (pintype "passive"))
    )
    (net (code "225") (name "/USART2_RX") (class "Default")
      (node (ref "U13") (pin "D2") (pinfunction "PD6_D2") (pintype "passive"))
    )
    (net (code "226") (name "/USART2_TX") (class "Default")
      (node (ref "U13") (pin "A7") (pinfunction "PD5_A7") (pintype "passive"))
    )
    (net (code "227") (name "/USART3_CTS") (class "Default")
      (node (ref "U13") (pin "AA10") (pinfunction "PB13_AA10") (pintype "passive"))
    )
    (net (code "228") (name "/USART3_RTS") (class "Default")
      (node (ref "U13") (pin "AB9") (pinfunction "PG8_AB9") (pintype "passive"))
    )
    (net (code "229") (name "/USART3_RX") (class "Default")
      (node (ref "U13") (pin "AC5") (pinfunction "PB12_AC5") (pintype "passive"))
    )
    (net (code "230") (name "/USART3_TX") (class "Default")
      (node (ref "U13") (pin "Y3") (pinfunction "PB10_Y3") (pintype "passive"))
    )
    (net (code "231") (name "/USB1_N") (class "Default")
      (node (ref "U13") (pin "AB17") (pinfunction "USB_DM1_AB17") (pintype "passive"))
    )
    (net (code "232") (name "/USB1_P") (class "Default")
      (node (ref "U13") (pin "AC17") (pinfunction "USB_DP1_AC17") (pintype "passive"))
    )
    (net (code "233") (name "/USB2_N") (class "Default")
      (node (ref "U13") (pin "AB16") (pinfunction "USB_DM2_AB16") (pintype "passive"))
    )
    (net (code "234") (name "/USB2_P") (class "Default")
      (node (ref "U13") (pin "AC16") (pinfunction "USB_DP2_AC16") (pintype "passive"))
    )
    (net (code "235") (name "/USB_PWR_CC1") (class "Default")
      (node (ref "U13") (pin "V4") (pinfunction "PA4_V4") (pintype "passive"))
    )
    (net (code "236") (name "/USB_PWR_CC2") (class "Default")
      (node (ref "U13") (pin "V3") (pinfunction "PA5_V3") (pintype "passive"))
    )
    (net (code "237") (name "/WL_HOST_WAKE") (class "Default")
      (node (ref "U13") (pin "B8") (pinfunction "PD0_B8") (pintype "passive"))
    )
    (net (code "238") (name "/WL_REG_ON") (class "Default")
      (node (ref "U13") (pin "B3") (pinfunction "PH4_B3") (pintype "passive"))
    )
    (net (code "239") (name "/uSD_DETECT") (class "Default")
      (node (ref "U13") (pin "D11") (pinfunction "PB7_D11") (pintype "passive"))
    )
    (net (code "252") (name "3V3") (class "Default")
      (node (ref "R1") (pin "1") (pinfunction "1_1") (pintype "passive"))
      (node (ref "R166") (pin "1") (pinfunction "1_1") (pintype "passive"))
      (node (ref "R167") (pin "1") (pinfunction "1_1") (pintype "passive"))
      (node (ref "R2") (pin "1") (pinfunction "1_1") (pintype "passive"))
      (node (ref "R300") (pin "1") (pinfunction "1_1") (pintype "passive"))
      (node (ref "R40") (pin "1") (pinfunction "1_1") (pintype "passive"))
    )
    (net (code "253") (name "GND") (class "Default")
      (node (ref "C300") (pin "1") (pinfunction "1_1") (pintype "passive"))
      (node (ref "C68") (pin "1") (pinfunction "1_1") (pintype "passive"))
      (node (ref "C87") (pin "2") (pinfunction "2_2") (pintype "passive"))
      (node (ref "C88") (pin "1") (pinfunction "1_1") (pintype "passive"))
      (node (ref "C90") (pin "2") (pinfunction "2_2") (pintype "passive"))
      (node (ref "C91") (pin "2") (pinfunction "2_2") (pintype "passive"))
      (node (ref "C92") (pin "1") (pinfunction "1_1") (pintype "passive"))
      (node (ref "R303") (pin "2") (pinfunction "2_2") (pintype "passive"))
      (node (ref "R38") (pin "2") (pinfunction "2_2") (pintype "passive"))
      (node (ref "R44") (pin "1") (pinfunction "1_1") (pintype "passive"))
      (node (ref "SB11") (pin "1") (pinfunction "1_1") (pintype "passive"))
      (node (ref "SB12") (pin "1") (pinfunction "1_1") (pintype "passive"))
      (node (ref "TP2") (pin "1") (pinfunction "1_1") (pintype "passive"))
      (node (ref "U13") (pin "AB13") (pinfunction "BYPASS_REG1V8_AB13") (pintype "passive"))
      (node (ref "X6") (pin "2") (pinfunction "GND_2") (pintype "passive"))
    )
    (net (code "254") (name "Net-(U13A-PC14-OSC32_IN)") (class "Default")
      (node (ref "C90") (pin "1") (pinfunction "1_1") (pintype "passive"))
      (node (ref "U13") (pin "L2") (pinfunction "PC14-OSC32_IN_L2") (pintype "passive"))
      (node (ref "X4") (pin "2") (pinfunction "X2_2") (pintype "passive"))
    )
    (net (code "255") (name "Net-(U13A-PC15-OSC32_OUT)") (class "Default")
      (node (ref "R71") (pin "1") (pinfunction "1_1") (pintype "passive"))
      (node (ref "U13") (pin "L1") (pinfunction "PC15-OSC32_OUT_L1") (pintype "passive"))
    )
    (net (code "256") (name "Net-(U13A-USB_RREF)") (class "Default")
      (node (ref "R44") (pin "2") (pinfunction "2_2") (pintype "passive"))
      (node (ref "U13") (pin "AB18") (pinfunction "USB_RREF_AB18") (pintype "passive"))
    )
    (net (code "257") (name "Net-(U13C-NRST_CORE)") (class "Default")
      (node (ref "C92") (pin "2") (pinfunction "2_2") (pintype "passive"))
      (node (ref "TP22") (pin "1") (pinfunction "1_1") (pintype "passive"))
      (node (ref "U13") (pin "M4") (pinfunction "NRST_CORE_M4") (pintype "passive"))
    )
    (net (code "258") (name "Net-(U13C-PDR_ON)") (class "Default")
      (node (ref "SB10") (pin "1") (pinfunction "1_1") (pintype "passive"))
      (node (ref "SB11") (pin "2") (pinfunction "2_2") (pintype "passive"))
      (node (ref "U13") (pin "R3") (pinfunction "PDR_ON_R3") (pintype "passive"))
    )
    (net (code "259") (name "Net-(U13C-PDR_ON_CORE)") (class "Default")
      (node (ref "SB12") (pin "2") (pinfunction "2_2") (pintype "passive"))
      (node (ref "SB9") (pin "1") (pinfunction "1_1") (pintype "passive"))
      (node (ref "U13") (pin "T3") (pinfunction "PDR_ON_CORE_T3") (pintype "passive"))
    )
    (net (code "260") (name "Net-(U13C-PWR_LP)") (class "Default")
      (node (ref "TP23") (pin "1") (pinfunction "1_1") (pintype "passive"))
      (node (ref "U13") (pin "N3") (pinfunction "PWR_LP_N3") (pintype "passive"))
    )
    (net (code "261") (name "Net-(U13E-DDR_ATO)") (class "Default")
      (node (ref "TP14") (pin "1") (pinfunction "1_1") (pintype "passive"))
      (node (ref "U13") (pin "Y19") (pinfunction "DDR_ATO_Y19") (pintype "passive"))
    )
    (net (code "262") (name "Net-(U13E-DDR_DTO0)") (class "Default")
      (node (ref "TP10") (pin "1") (pinfunction "1_1") (pintype "passive"))
      (node (ref "U13") (pin "K20") (pinfunction "DDR_DTO0_K20") (pintype "passive"))
    )
    (net (code "263") (name "Net-(U13E-DDR_DTO1)") (class "Default")
      (node (ref "TP13") (pin "1") (pinfunction "1_1") (pintype "passive"))
      (node (ref "U13") (pin "L21") (pinfunction "DDR_DTO1_L21") (pintype "passive"))
    )
    (net (code "264") (name "Net-(U13E-DDR_ZQ)") (class "Default")
      (node (ref "R38") (pin "1") (pinfunction "1_1") (pintype "passive"))
      (node (ref "U13") (pin "K23") (pinfunction "DDR_ZQ_K23") (pintype "passive"))
    )
    (net (code "265") (name "Net-(X4-X1)") (class "Default")
      (node (ref "C91") (pin "1") (pinfunction "1_1") (pintype "passive"))
      (node (ref "R71") (pin "2") (pinfunction "2_2") (pintype "passive"))
      (node (ref "X4") (pin "1") (pinfunction "X1_1") (pintype "passive"))
    )
    (net (code "266") (name "Net-(X6-EN)") (class "Default")
      (node (ref "C87") (pin "1") (pinfunction "1_1") (pintype "passive"))
      (node (ref "R302") (pin "1") (pinfunction "1_1") (pintype "passive"))
      (node (ref "R73") (pin "1") (pinfunction "1_1") (pintype "passive"))
      (node (ref "X6") (pin "1") (pinfunction "EN_1") (pintype "passive"))
    )
    (net (code "267") (name "Net-(X6-VDD)") (class "Default")
      (node (ref "C300") (pin "2") (pinfunction "2_2") (pintype "passive"))
      (node (ref "R304") (pin "2") (pinfunction "2_2") (pintype "passive"))
      (node (ref "X6") (pin "4") (pinfunction "VDD_4") (pintype "passive"))
    )
    (net (code "268") (name "VDD") (class "Default")
      (node (ref "R304") (pin "1") (pinfunction "1_1") (pintype "passive"))
      (node (ref "R5") (pin "1") (pinfunction "1_1") (pintype "passive"))
      (node (ref "R7") (pin "1") (pinfunction "1_1") (pintype "passive"))
      (node (ref "SB10") (pin "2") (pinfunction "2_2") (pintype "passive"))
      (node (ref "SB9") (pin "2") (pinfunction "2_2") (pintype "passive"))
    )
    (net (code "269") (name "VREF_DDR") (class "Default")
      (node (ref "C68") (pin "2") (pinfunction "2_2") (pintype "passive"))
      (node (ref "U13") (pin "AC20") (pinfunction "DDR_VREF_AC20") (pintype "passive"))
    )
    (net (code "270") (name "unconnected-(SB1-Pad1)") (class "Default")
      (node (ref "SB1") (pin "1") (pinfunction "1_1") (pintype "passive"))
    )
    (net (code "271") (name "unconnected-(SB2-Pad1)") (class "Default")
      (node (ref "SB2") (pin "1") (pinfunction "1_1") (pintype "passive"))
    )
    (net (code "272") (name "unconnected-(SB3-Pad1)") (class "Default")
      (node (ref "SB3") (pin "1") (pinfunction "1_1") (pintype "passive"))
    )
    (net (code "273") (name "unconnected-(SB4-Pad1)") (class "Default")
      (node (ref "SB4") (pin "1") (pinfunction "1_1") (pintype "passive"))
    )
    (net (code "274") (name "unconnected-(SB13-Pad1)") (class "Default")
      (node (ref "SB13") (pin "1") (pinfunction "1_1") (pintype "passive"))
    )
    (net (code "275") (name "unconnected-(SB14-Pad1)") (class "Default")
      (node (ref "SB14") (pin "1") (pinfunction "1_1") (pintype "passive"))
    )
    (net (code "276") (name "unconnected-(SB15-Pad1)") (class "Default")
      (node (ref "SB15") (pin "1") (pinfunction "1_1") (pintype "passive"))
    )
    (net (code "277") (name "unconnected-(SB16-Pad1)") (class "Default")
      (node (ref "SB16") (pin "1") (pinfunction "1_1") (pintype "passive"))
    )
    (net (code "278") (name "unconnected-(U13A-OTG_VBUS-PadAC19)") (class "Default")
      (node (ref "U13") (pin "AC19") (pinfunction "OTG_VBUS_AC19") (pintype "passive+no_connect"))
    )
    (net (code "279") (name "unconnected-(U13E-DDR_A15-PadP20)") (class "Default")
      (node (ref "U13") (pin "P20") (pinfunction "DDR_A15_P20") (pintype "passive+no_connect"))
    )
    (net (code "280") (name "unconnected-(U13E-DDR_DQ16-PadB22)") (class "Default")
      (node (ref "U13") (pin "B22") (pinfunction "DDR_DQ16_B22") (pintype "passive+no_connect"))
    )
    (net (code "281") (name "unconnected-(U13E-DDR_DQ17-PadD22)") (class "Default")
      (node (ref "U13") (pin "D22") (pinfunction "DDR_DQ17_D22") (pintype "passive+no_connect"))
    )
    (net (code "282") (name "unconnected-(U13E-DDR_DQ18-PadD23)") (class "Default")
      (node (ref "U13") (pin "D23") (pinfunction "DDR_DQ18_D23") (pintype "passive+no_connect"))
    )
    (net (code "283") (name "unconnected-(U13E-DDR_DQ19-PadB21)") (class "Default")
      (node (ref "U13") (pin "B21") (pinfunction "DDR_DQ19_B21") (pintype "passive+no_connect"))
    )
    (net (code "284") (name "unconnected-(U13E-DDR_DQ20-PadA21)") (class "Default")
      (node (ref "U13") (pin "A21") (pinfunction "DDR_DQ20_A21") (pintype "passive+no_connect"))
    )
    (net (code "285") (name "unconnected-(U13E-DDR_DQ21-PadE23)") (class "Default")
      (node (ref "U13") (pin "E23") (pinfunction "DDR_DQ21_E23") (pintype "passive+no_connect"))
    )
    (net (code "286") (name "unconnected-(U13E-DDR_DQ22-PadD21)") (class "Default")
      (node (ref "U13") (pin "D21") (pinfunction "DDR_DQ22_D21") (pintype "passive+no_connect"))
    )
    (net (code "287") (name "unconnected-(U13E-DDR_DQ23-PadA22)") (class "Default")
      (node (ref "U13") (pin "A22") (pinfunction "DDR_DQ23_A22") (pintype "passive+no_connect"))
    )
    (net (code "288") (name "unconnected-(U13E-DDR_DQ24-PadY23)") (class "Default")
      (node (ref "U13") (pin "Y23") (pinfunction "DDR_DQ24_Y23") (pintype "passive+no_connect"))
    )
    (net (code "289") (name "unconnected-(U13E-DDR_DQ25-PadY22)") (class "Default")
      (node (ref "U13") (pin "Y22") (pinfunction "DDR_DQ25_Y22") (pintype "passive+no_connect"))
    )
    (net (code "290") (name "unconnected-(U13E-DDR_DQ26-PadAB21)") (class "Default")
      (node (ref "U13") (pin "AB21") (pinfunction "DDR_DQ26_AB21") (pintype "passive+no_connect"))
    )
    (net (code "291") (name "unconnected-(U13E-DDR_DQ27-PadAB20)") (class "Default")
      (node (ref "U13") (pin "AB20") (pinfunction "DDR_DQ27_AB20") (pintype "passive+no_connect"))
    )
    (net (code "292") (name "unconnected-(U13E-DDR_DQ28-PadAC22)") (class "Default")
      (node (ref "U13") (pin "AC22") (pinfunction "DDR_DQ28_AC22") (pintype "passive+no_connect"))
    )
    (net (code "293") (name "unconnected-(U13E-DDR_DQ29-PadAC21)") (class "Default")
      (node (ref "U13") (pin "AC21") (pinfunction "DDR_DQ29_AC21") (pintype "passive+no_connect"))
    )
    (net (code "294") (name "unconnected-(U13E-DDR_DQ30-PadAA23)") (class "Default")
      (node (ref "U13") (pin "AA23") (pinfunction "DDR_DQ30_AA23") (pintype "passive+no_connect"))
    )
    (net (code "295") (name "unconnected-(U13E-DDR_DQ31-PadAA22)") (class "Default")
      (node (ref "U13") (pin "AA22") (pinfunction "DDR_DQ31_AA22") (pintype "passive+no_connect"))
    )
    (net (code "296") (name "unconnected-(U13E-DDR_DQM2-PadC23)") (class "Default")
      (node (ref "U13") (pin "C23") (pinfunction "DDR_DQM2_C23") (pintype "passive+no_connect"))
    )
    (net (code "297") (name "unconnected-(U13E-DDR_DQM3-PadAA20)") (class "Default")
      (node (ref "U13") (pin "AA20") (pinfunction "DDR_DQM3_AA20") (pintype "passive+no_connect"))
    )
    (net (code "298") (name "unconnected-(U13E-DDR_DQS2N-PadB23)") (class "Default")
      (node (ref "U13") (pin "B23") (pinfunction "DDR_DQS2N_B23") (pintype "passive+no_connect"))
    )
    (net (code "299") (name "unconnected-(U13E-DDR_DQS2P-PadC22)") (class "Default")
      (node (ref "U13") (pin "C22") (pinfunction "DDR_DQS2P_C22") (pintype "passive+no_connect"))
    )
    (net (code "300") (name "unconnected-(U13E-DDR_DQS3N-PadAB23)") (class "Default")
      (node (ref "U13") (pin "AB23") (pinfunction "DDR_DQS3N_AB23") (pintype "passive+no_connect"))
    )
    (net (code "301") (name "unconnected-(U13E-DDR_DQS3P-PadAB22)") (class "Default")
      (node (ref "U13") (pin "AB22") (pinfunction "DDR_DQS3P_AB22") (pintype "passive+no_connect"))
    )
  )
)
